# TemperatureMonitor-DS18B20.net
KiCad netlist of a schematic drawn in EAGLE
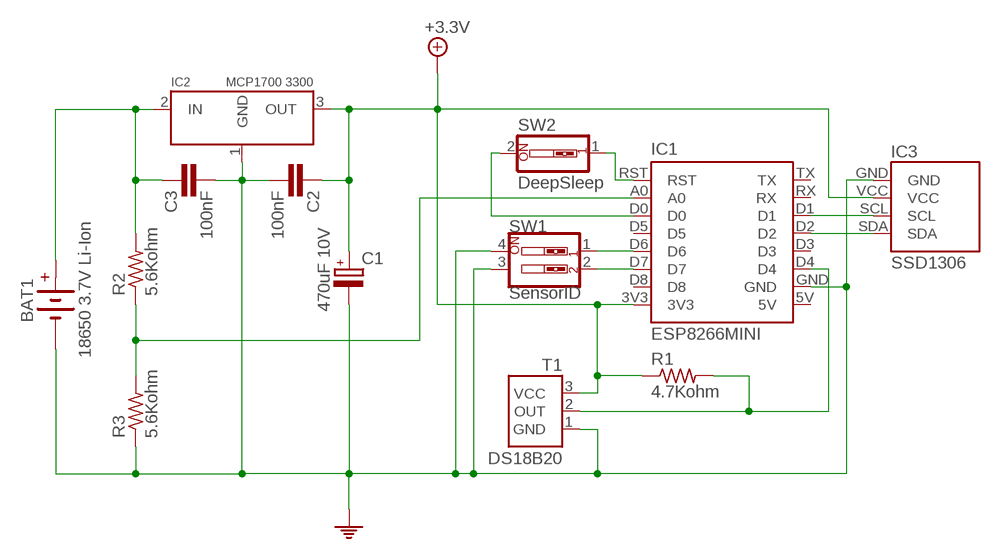
[diagram p0: schematic, sheet 1]

(export (version "E")
  (design (tool "Eeschema 10.0.6"))
  (components
    (comp (ref "BAT1")
      (value "18650 3.7V Li-Ion")
      (footprint "eagle-import:SIL2")
      (libsource (lib "eagle-import") (part "BATTERYSIL2"))
    )
    (comp (ref "C1")
      (value "470uF 10V")
      (footprint "eagle-import:CAPACITOR-5MM")
      (libsource (lib "eagle-import") (part "CAPACITOR_EL5MM"))
    )
    (comp (ref "C2")
      (value "100nF")
      (footprint "eagle-import:CAPACITOR-5MM")
      (libsource (lib "eagle-import") (part "CAPACITOR5MM"))
    )
    (comp (ref "C3")
      (value "100nF")
      (footprint "eagle-import:CAPACITOR-5MM")
      (libsource (lib "eagle-import") (part "CAPACITOR5MM"))
    )
    (comp (ref "IC1")
      (value "ESP8266MINI")
      (footprint "eagle-import:ESP8266MINI")
      (libsource (lib "eagle-import") (part "ESP8266MINI"))
    )
    (comp (ref "IC2")
      (value "MCP1700 3300")
      (footprint "eagle-import:TO92")
      (libsource (lib "eagle-import") (part "MCP1700"))
    )
    (comp (ref "IC3")
      (value "SSD1306")
      (footprint "eagle-import:SSD1306")
      (libsource (lib "eagle-import") (part "SSD1306"))
    )
    (comp (ref "R1")
      (value "4.7Kohm")
      (footprint "eagle-import:RESISTOR-0.25W")
      (libsource (lib "eagle-import") (part "RESISTOR0.25W"))
    )
    (comp (ref "R2")
      (value "5.6Kohm")
      (footprint "eagle-import:RESISTOR-0.25W")
      (libsource (lib "eagle-import") (part "RESISTOR0.25W"))
    )
    (comp (ref "R3")
      (value "5.6Kohm")
      (footprint "eagle-import:RESISTOR-0.25W")
      (libsource (lib "eagle-import") (part "RESISTOR0.25W"))
    )
    (comp (ref "SW1")
      (value "SensorID")
      (footprint "eagle-import:DIL4")
      (libsource (lib "eagle-import") (part "DIP-SWITCH-2"))
    )
    (comp (ref "SW2")
      (value "DeepSleep")
      (footprint "eagle-import:DIL2")
      (libsource (lib "eagle-import") (part "DIP-SWITCH-1"))
    )
    (comp (ref "T1")
      (value "DS18B20")
      (footprint "eagle-import:TO92")
      (libsource (lib "eagle-import") (part "DS18B20"))
    )
  )
  (nets
    (net (code "1") (name "+3.3V") (class "Default")
      (node (ref "C1") (pin "1") (pinfunction "1_1") (pintype "passive"))
      (node (ref "C2") (pin "1") (pinfunction "1_1") (pintype "passive"))
      (node (ref "IC1") (pin "3V3") (pinfunction "3V3_3V3") (pintype "power_in"))
      (node (ref "IC2") (pin "3") (pinfunction "OUT_3") (pintype "output"))
      (node (ref "IC3") (pin "VCC") (pinfunction "VCC_VCC") (pintype "power_in"))
      (node (ref "R1") (pin "1") (pinfunction "1_1") (pintype "passive"))
      (node (ref "T1") (pin "3") (pinfunction "VCC_3") (pintype "power_in"))
    )
    (net (code "2") (name "/5V") (class "Default")
      (node (ref "IC1") (pin "5V") (pinfunction "5V_5V") (pintype "power_in"))
    )
    (net (code "3") (name "GND") (class "Default")
      (node (ref "BAT1") (pin "2") (pinfunction "-_2") (pintype "passive"))
      (node (ref "C1") (pin "2") (pinfunction "2_2") (pintype "passive"))
      (node (ref "C2") (pin "2") (pinfunction "2_2") (pintype "passive"))
      (node (ref "C3") (pin "1") (pinfunction "1_1") (pintype "passive"))
      (node (ref "IC1") (pin "GND") (pinfunction "GND_GND") (pintype "power_in"))
      (node (ref "IC2") (pin "1") (pinfunction "GND_1") (pintype "power_in"))
      (node (ref "IC3") (pin "GND") (pinfunction "GND_GND") (pintype "power_in"))
      (node (ref "R3") (pin "1") (pinfunction "1_1") (pintype "passive"))
      (node (ref "SW1") (pin "3") (pinfunction "3_3") (pintype "passive"))
      (node (ref "SW1") (pin "4") (pinfunction "4_4") (pintype "passive"))
      (node (ref "T1") (pin "1") (pinfunction "GND_1") (pintype "power_in"))
    )
    (net (code "4") (name "Net-(BAT1-+)") (class "Default")
      (node (ref "BAT1") (pin "1") (pinfunction "+_1") (pintype "passive"))
      (node (ref "C3") (pin "2") (pinfunction "2_2") (pintype "passive"))
      (node (ref "IC2") (pin "2") (pinfunction "IN_2") (pintype "input"))
      (node (ref "R2") (pin "2") (pinfunction "2_2") (pintype "passive"))
    )
    (net (code "5") (name "Net-(IC1-PadA0)") (class "Default")
      (node (ref "IC1") (pin "A0") (pinfunction "A0_A0") (pintype "bidirectional"))
      (node (ref "R2") (pin "1") (pinfunction "1_1") (pintype "passive"))
      (node (ref "R3") (pin "2") (pinfunction "2_2") (pintype "passive"))
    )
    (net (code "6") (name "Net-(IC1-PadD0)") (class "Default")
      (node (ref "IC1") (pin "D0") (pinfunction "D0_D0") (pintype "bidirectional"))
      (node (ref "SW2") (pin "2") (pinfunction "2_2") (pintype "passive"))
    )
    (net (code "7") (name "Net-(IC1-PadD1)") (class "Default")
      (node (ref "IC1") (pin "D1") (pinfunction "D1_D1") (pintype "bidirectional"))
      (node (ref "IC3") (pin "SCL") (pinfunction "SCL_SCL") (pintype "bidirectional"))
    )
    (net (code "8") (name "Net-(IC1-PadD2)") (class "Default")
      (node (ref "IC1") (pin "D2") (pinfunction "D2_D2") (pintype "bidirectional"))
      (node (ref "IC3") (pin "SDA") (pinfunction "SDA_SDA") (pintype "bidirectional"))
    )
    (net (code "9") (name "Net-(IC1-PadD6)") (class "Default")
      (node (ref "IC1") (pin "D6") (pinfunction "D6_D6") (pintype "bidirectional"))
      (node (ref "SW1") (pin "1") (pinfunction "1_1") (pintype "passive"))
    )
    (net (code "10") (name "Net-(IC1-PadD7)") (class "Default")
      (node (ref "IC1") (pin "D7") (pinfunction "D7_D7") (pintype "bidirectional"))
      (node (ref "SW1") (pin "2") (pinfunction "2_2") (pintype "passive"))
    )
    (net (code "11") (name "Net-(IC1-PadRST)") (class "Default")
      (node (ref "IC1") (pin "RST") (pinfunction "RST_RST") (pintype "bidirectional"))
      (node (ref "SW2") (pin "1") (pinfunction "1_1") (pintype "passive"))
    )
    (net (code "12") (name "Net-(T1-OUT)") (class "Default")
      (node (ref "IC1") (pin "D4") (pinfunction "D4_D4") (pintype "bidirectional"))
      (node (ref "R1") (pin "2") (pinfunction "2_2") (pintype "passive"))
      (node (ref "T1") (pin "2") (pinfunction "OUT_2") (pintype "output"))
    )
    (net (code "13") (name "unconnected-(IC1-PadD3)") (class "Default")
      (node (ref "IC1") (pin "D3") (pinfunction "D3_D3") (pintype "bidirectional"))
    )
    (net (code "14") (name "unconnected-(IC1-PadD5)") (class "Default")
      (node (ref "IC1") (pin "D5") (pinfunction "D5_D5") (pintype "bidirectional"))
    )
    (net (code "15") (name "unconnected-(IC1-PadD8)") (class "Default")
      (node (ref "IC1") (pin "D8") (pinfunction "D8_D8") (pintype "bidirectional"))
    )
    (net (code "16") (name "unconnected-(IC1-PadRX)") (class "Default")
      (node (ref "IC1") (pin "RX") (pinfunction "RX_RX") (pintype "input"))
    )
    (net (code "17") (name "unconnected-(IC1-PadTX)") (class "Default")
      (node (ref "IC1") (pin "TX") (pinfunction "TX_TX") (pintype "output"))
    )
  )
)
